# motor_controller_interface.net
KiCad netlist of a schematic drawn in Altium Designer
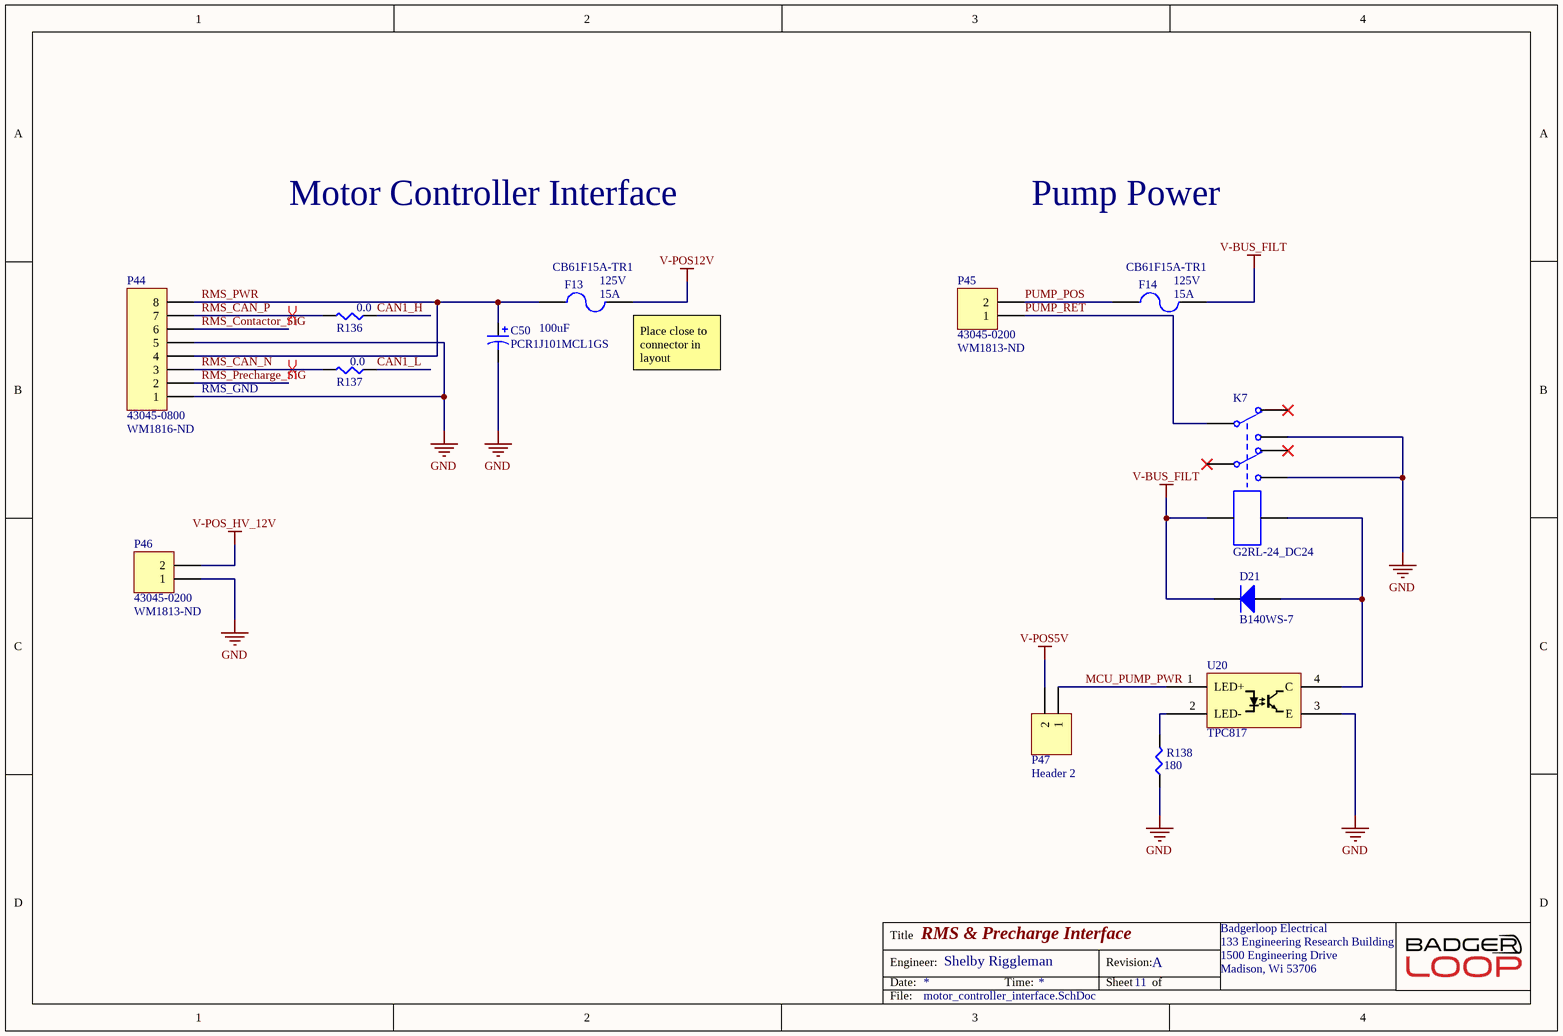
[diagram p0: motor_controller_interface.SchDoc]

(export (version "E")
  (design (tool "Eeschema 10.0.6"))
  (components
    (comp (ref "C50")
      (value "PCR1J101MCL1GS")
      (footprint "CAPAE110103X126M")
      (description "CAP ALUM POLY 100UF 20% 63V SMD")
      (fields
        (field (name "MANUFACTURER") "Nichicon")
        (field (name "CAPACITANCE") "100uF")
        (field (name "TOLERANCE") "20%")
      )
      (libsource (lib "capacitors") (part "PCR1J101MCL1GS"))
    )
    (comp (ref "D21")
      (value "B140WS-7")
      (footprint "SODFL250X110-2N")
      (description "Diode Schottky 40V 1A 2-Pin SOD-323 T/R")
      (fields (field (name "MANUFACTURER") "Diodes"))
      (libsource (lib "misc") (part "B140WS-7"))
    )
    (comp (ref "F13")
      (value "CB61F15A-TR1")
      (footprint "RESC6132X26N")
      (fields
        (field (name "MANUFACTURER") "Eaton")
        (field (name "CURRENT RATING") "15A")
        (field (name "VOLTAGE RATING") "125V")
      )
      (libsource (lib "misc") (part "CB61F15A-TR1"))
    )
    (comp (ref "F14")
      (value "CB61F15A-TR1")
      (footprint "RESC6132X26N")
      (fields
        (field (name "MANUFACTURER") "Eaton")
        (field (name "CURRENT RATING") "15A")
        (field (name "VOLTAGE RATING") "125V")
      )
      (libsource (lib "misc") (part "CB61F15A-TR1"))
    )
    (comp (ref "K7")
      (value "G2RL-24_DC24")
      (footprint "G2RL")
      (description "RELAY GEN PURPOSE DPDT 8A 24V")
      (fields (field (name "MANUFACTURER") "Omron") (field (name "MANUFACTURER PART NUMBER") "G2RL-24-DC24"))
      (libsource (lib "misc") (part "G2RL-24_DC24"))
    )
    (comp (ref "P44")
      (value "43045-0800")
      (footprint "430450800")
      (description "CONN HEADER R/A 8POS 3MM")
      (fields (field (name "MANUFACTURER") "Molex") (field (name "SUPPLIER PART NUMBER 1") "WM1816-ND"))
      (libsource (lib "connector") (part "43045-0800"))
    )
    (comp (ref "P45")
      (value "43045-0200")
      (footprint "430450200")
      (description "CONN HEADER R/A 2POS")
      (fields (field (name "MANUFACTURER") "Molex") (field (name "SUPPLIER PART NUMBER 1") "WM1813-ND"))
      (libsource (lib "connector") (part "43045-0200"))
    )
    (comp (ref "P46")
      (value "43045-0200")
      (footprint "430450200")
      (description "CONN HEADER R/A 2POS")
      (fields (field (name "MANUFACTURER") "Molex") (field (name "SUPPLIER PART NUMBER 1") "WM1813-ND"))
      (libsource (lib "connector") (part "43045-0200"))
    )
    (comp (ref "P47")
      (value "Header 2")
      (footprint "Pin Header 1x2 TH Pitch 2.54mm")
      (description "Header, 2-Pin")
      (fields (field (name "PUBLISHER") "Altium Limited"))
      (libsource (lib "connector") (part "Header 2"))
    )
    (comp (ref "R136")
      (value "0.0")
      (footprint "SMD-0805-RES")
      (description "RES SMD 0.0 OHM JUMPER 1/8W 0805")
      (fields (field (name "PART NUMBER") "ERJ-6GEY0R00V") (field (name "DIGI-KEY PART NUMBER") "P0.0ACT-ND"))
      (libsource (lib "resistors") (part "ERJ-6GEY0R00V"))
    )
    (comp (ref "R137")
      (value "0.0")
      (footprint "SMD-0805-RES")
      (description "RES SMD 0.0 OHM JUMPER 1/8W 0805")
      (fields (field (name "PART NUMBER") "ERJ-6GEY0R00V") (field (name "DIGI-KEY PART NUMBER") "P0.0ACT-ND"))
      (libsource (lib "resistors") (part "ERJ-6GEY0R00V"))
    )
    (comp (ref "R138")
      (value "180")
      (footprint "SMD-0805-RES")
      (description "RES SMD 180 OHM 1% 1/8W 0805")
      (fields (field (name "PART NUMBER") "ERJ-6ENF1800V") (field (name "DIGI-KEY PART NUMBER") "P180CCT-ND"))
      (libsource (lib "resistors") (part "ERJ-6ENF1800V"))
    )
    (comp (ref "U20")
      (value "TPC817")
      (footprint "SOT200P1005X328-5N")
      (description "OPTOISO 5KV TRANS 4SOP")
      (fields (field (name "MANUFACTURER") "Taiwan Semi"))
      (libsource (lib "ic") (part "TPC817"))
    )
  )
  (nets
    (net (code "1") (name "/CAN1_H") (class "Default")
      (node (ref "R136") (pin "1") (pinfunction "1_1") (pintype "passive"))
    )
    (net (code "2") (name "/CAN1_L") (class "Default")
      (node (ref "R137") (pin "1") (pinfunction "1_1") (pintype "passive"))
    )
    (net (code "3") (name "/MCU_PUMP_PWR") (class "Default")
      (node (ref "P47") (pin "1") (pinfunction "1_1") (pintype "passive"))
      (node (ref "U20") (pin "1") (pinfunction "LED+_1") (pintype "passive"))
    )
    (net (code "4") (name "/PUMP_POS") (class "Default")
      (node (ref "F14") (pin "1") (pinfunction "1_1") (pintype "passive"))
      (node (ref "P45") (pin "2") (pinfunction "2_2") (pintype "passive"))
    )
    (net (code "5") (name "/PUMP_RET") (class "Default")
      (node (ref "K7") (pin "3") (pinfunction "3_3") (pintype "passive"))
      (node (ref "P45") (pin "1") (pinfunction "1_1") (pintype "passive"))
    )
    (net (code "6") (name "/RMS_CAN_N") (class "Default")
      (node (ref "P44") (pin "3") (pinfunction "3_3") (pintype "passive"))
      (node (ref "R137") (pin "2") (pinfunction "2_2") (pintype "passive"))
    )
    (net (code "7") (name "/RMS_CAN_P") (class "Default")
      (node (ref "P44") (pin "7") (pinfunction "7_7") (pintype "passive"))
      (node (ref "R136") (pin "2") (pinfunction "2_2") (pintype "passive"))
    )
    (net (code "8") (name "/RMS_Contactor_SIG") (class "Default")
      (node (ref "P44") (pin "6") (pinfunction "6_6") (pintype "passive"))
    )
    (net (code "9") (name "/RMS_PWR") (class "Default")
      (node (ref "C50") (pin "1") (pinfunction "1_1") (pintype "passive"))
      (node (ref "F13") (pin "1") (pinfunction "1_1") (pintype "passive"))
      (node (ref "P44") (pin "4") (pinfunction "4_4") (pintype "passive"))
      (node (ref "P44") (pin "8") (pinfunction "8_8") (pintype "passive"))
    )
    (net (code "10") (name "/RMS_Precharge_SIG") (class "Default")
      (node (ref "P44") (pin "2") (pinfunction "2_2") (pintype "passive"))
    )
    (net (code "11") (name "GND") (class "Default")
      (node (ref "C50") (pin "2") (pinfunction "2_2") (pintype "passive"))
      (node (ref "K7") (pin "4") (pinfunction "4_4") (pintype "passive"))
      (node (ref "K7") (pin "5") (pinfunction "5_5") (pintype "passive"))
      (node (ref "P44") (pin "1") (pinfunction "1_1") (pintype "passive"))
      (node (ref "P44") (pin "5") (pinfunction "5_5") (pintype "passive"))
      (node (ref "P46") (pin "1") (pinfunction "1_1") (pintype "passive"))
      (node (ref "R138") (pin "1") (pinfunction "1_1") (pintype "passive"))
      (node (ref "U20") (pin "3") (pinfunction "E_3") (pintype "passive"))
    )
    (net (code "12") (name "Net-(D21-A)") (class "Default")
      (node (ref "D21") (pin "1") (pinfunction "A_1") (pintype "passive"))
      (node (ref "K7") (pin "8") (pinfunction "8_8") (pintype "passive"))
      (node (ref "U20") (pin "4") (pinfunction "C_4") (pintype "passive"))
    )
    (net (code "13") (name "Net-(U20-LED-)") (class "Default")
      (node (ref "R138") (pin "2") (pinfunction "2_2") (pintype "passive"))
      (node (ref "U20") (pin "2") (pinfunction "LED-_2") (pintype "passive"))
    )
    (net (code "14") (name "V-BUS_FILT") (class "Default")
      (node (ref "D21") (pin "2") (pinfunction "K_2") (pintype "passive"))
      (node (ref "F14") (pin "2") (pinfunction "2_2") (pintype "passive"))
      (node (ref "K7") (pin "1") (pinfunction "1_1") (pintype "passive"))
    )
    (net (code "15") (name "V-POS5V") (class "Default")
      (node (ref "P47") (pin "2") (pinfunction "2_2") (pintype "passive"))
    )
    (net (code "16") (name "V-POS12V") (class "Default")
      (node (ref "F13") (pin "2") (pinfunction "2_2") (pintype "passive"))
    )
    (net (code "17") (name "V-POS_HV_12V") (class "Default")
      (node (ref "P46") (pin "2") (pinfunction "2_2") (pintype "passive"))
    )
    (net (code "18") (name "unconnected-(K7-Pad2)") (class "Default")
      (node (ref "K7") (pin "2") (pinfunction "2_2") (pintype "passive+no_connect"))
    )
    (net (code "19") (name "unconnected-(K7-Pad6)") (class "Default")
      (node (ref "K7") (pin "6") (pinfunction "6_6") (pintype "passive+no_connect"))
    )
    (net (code "20") (name "unconnected-(K7-Pad7)") (class "Default")
      (node (ref "K7") (pin "7") (pinfunction "7_7") (pintype "passive+no_connect"))
    )
  )
)
